# bus.net
KiCad netlist of a schematic drawn in EAGLE
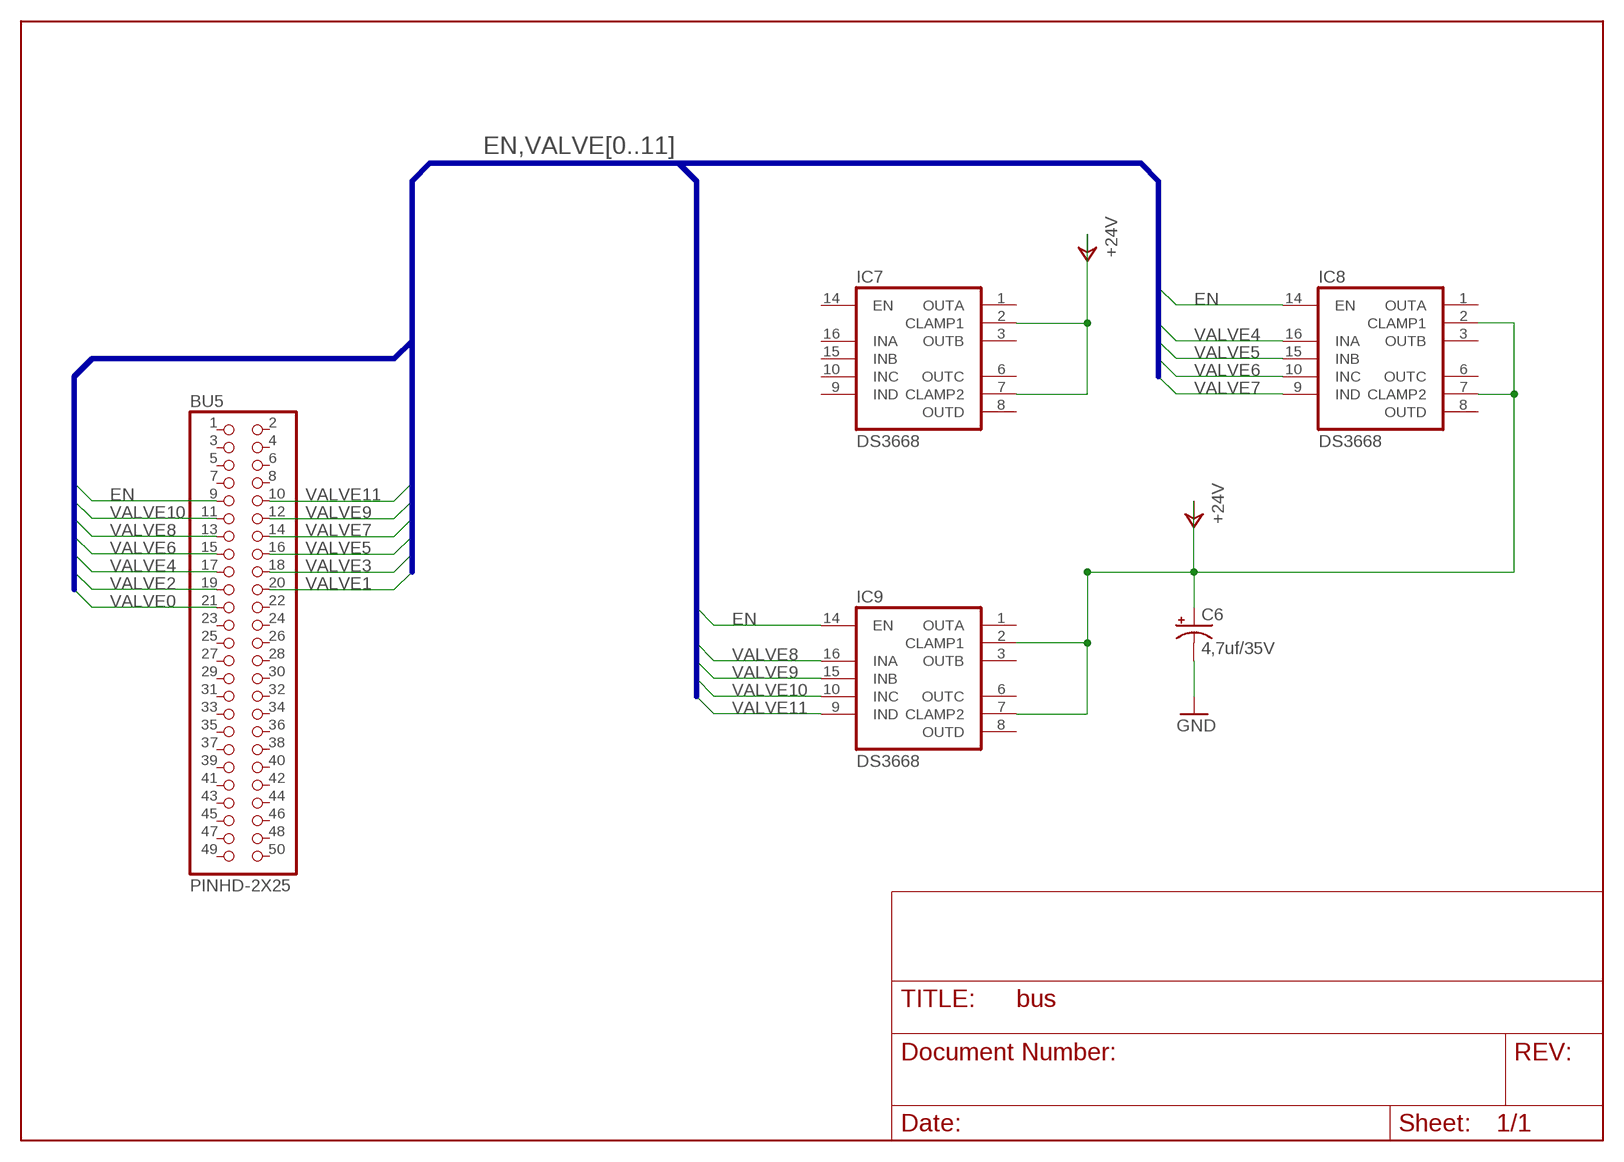
[diagram p0: schematic, sheet 1]

(export (version "E")
  (design (tool "Eeschema 10.0.6"))
  (components
    (comp (ref "BU5")
      (value "PINHD-2X25")
      (footprint "eagle-import:2X25")
      (libsource (lib "eagle-import") (part "PINHD-2X25"))
    )
    (comp (ref "C6")
      (value "4,7uf/35V")
      (footprint "eagle-import:E2,5-6")
      (libsource (lib "eagle-import") (part "CPOL-USE2.5-6"))
    )
    (comp (ref "IC7")
      (value "DS3668")
      (footprint "eagle-import:DIL-16")
      (libsource (lib "eagle-import") (part "DS3668"))
    )
    (comp (ref "IC8")
      (value "DS3668")
      (footprint "eagle-import:DIL-16")
      (libsource (lib "eagle-import") (part "DS3668"))
    )
    (comp (ref "IC9")
      (value "DS3668")
      (footprint "eagle-import:DIL-16")
      (libsource (lib "eagle-import") (part "DS3668"))
    )
  )
  (nets
    (net (code "13") (name "+24V") (class "Default")
      (node (ref "C6") (pin "+") (pinfunction "+_+") (pintype "passive"))
      (node (ref "IC7") (pin "2") (pinfunction "CLAMP1_2") (pintype "bidirectional"))
      (node (ref "IC7") (pin "7") (pinfunction "CLAMP2_7") (pintype "bidirectional"))
      (node (ref "IC8") (pin "2") (pinfunction "CLAMP1_2") (pintype "bidirectional"))
      (node (ref "IC8") (pin "7") (pinfunction "CLAMP2_7") (pintype "bidirectional"))
      (node (ref "IC9") (pin "2") (pinfunction "CLAMP1_2") (pintype "bidirectional"))
      (node (ref "IC9") (pin "7") (pinfunction "CLAMP2_7") (pintype "bidirectional"))
    )
    (net (code "14") (name "/EN") (class "Default")
      (node (ref "BU5") (pin "9") (pinfunction "9_9") (pintype "passive"))
      (node (ref "IC8") (pin "14") (pinfunction "EN_14") (pintype "input"))
      (node (ref "IC9") (pin "14") (pinfunction "EN_14") (pintype "input"))
    )
    (net (code "16") (name "/VALVE0") (class "Default")
      (node (ref "BU5") (pin "21") (pinfunction "21_21") (pintype "passive"))
    )
    (net (code "17") (name "/VALVE1") (class "Default")
      (node (ref "BU5") (pin "20") (pinfunction "20_20") (pintype "passive"))
    )
    (net (code "18") (name "/VALVE2") (class "Default")
      (node (ref "BU5") (pin "19") (pinfunction "19_19") (pintype "passive"))
    )
    (net (code "19") (name "/VALVE3") (class "Default")
      (node (ref "BU5") (pin "18") (pinfunction "18_18") (pintype "passive"))
    )
    (net (code "20") (name "/VALVE4") (class "Default")
      (node (ref "BU5") (pin "17") (pinfunction "17_17") (pintype "passive"))
      (node (ref "IC8") (pin "16") (pinfunction "INA_16") (pintype "input"))
    )
    (net (code "21") (name "/VALVE5") (class "Default")
      (node (ref "BU5") (pin "16") (pinfunction "16_16") (pintype "passive"))
      (node (ref "IC8") (pin "15") (pinfunction "INB_15") (pintype "input"))
    )
    (net (code "22") (name "/VALVE6") (class "Default")
      (node (ref "BU5") (pin "15") (pinfunction "15_15") (pintype "passive"))
      (node (ref "IC8") (pin "10") (pinfunction "INC_10") (pintype "input"))
    )
    (net (code "23") (name "/VALVE7") (class "Default")
      (node (ref "BU5") (pin "14") (pinfunction "14_14") (pintype "passive"))
      (node (ref "IC8") (pin "9") (pinfunction "IND_9") (pintype "input"))
    )
    (net (code "24") (name "/VALVE8") (class "Default")
      (node (ref "BU5") (pin "13") (pinfunction "13_13") (pintype "passive"))
      (node (ref "IC9") (pin "16") (pinfunction "INA_16") (pintype "input"))
    )
    (net (code "25") (name "/VALVE9") (class "Default")
      (node (ref "BU5") (pin "12") (pinfunction "12_12") (pintype "passive"))
      (node (ref "IC9") (pin "15") (pinfunction "INB_15") (pintype "input"))
    )
    (net (code "26") (name "/VALVE10") (class "Default")
      (node (ref "BU5") (pin "11") (pinfunction "11_11") (pintype "passive"))
      (node (ref "IC9") (pin "10") (pinfunction "INC_10") (pintype "input"))
    )
    (net (code "27") (name "/VALVE11") (class "Default")
      (node (ref "BU5") (pin "10") (pinfunction "10_10") (pintype "passive"))
      (node (ref "IC9") (pin "9") (pinfunction "IND_9") (pintype "input"))
    )
    (net (code "28") (name "GND") (class "Default")
      (node (ref "C6") (pin "-") (pinfunction "-_-") (pintype "passive"))
    )
    (net (code "29") (name "unconnected-(BU5-Pad1)") (class "Default")
      (node (ref "BU5") (pin "1") (pinfunction "1_1") (pintype "passive"))
    )
    (net (code "30") (name "unconnected-(BU5-Pad2)") (class "Default")
      (node (ref "BU5") (pin "2") (pinfunction "2_2") (pintype "passive"))
    )
    (net (code "31") (name "unconnected-(BU5-Pad3)") (class "Default")
      (node (ref "BU5") (pin "3") (pinfunction "3_3") (pintype "passive"))
    )
    (net (code "32") (name "unconnected-(BU5-Pad4)") (class "Default")
      (node (ref "BU5") (pin "4") (pinfunction "4_4") (pintype "passive"))
    )
    (net (code "33") (name "unconnected-(BU5-Pad5)") (class "Default")
      (node (ref "BU5") (pin "5") (pinfunction "5_5") (pintype "passive"))
    )
    (net (code "34") (name "unconnected-(BU5-Pad6)") (class "Default")
      (node (ref "BU5") (pin "6") (pinfunction "6_6") (pintype "passive"))
    )
    (net (code "35") (name "unconnected-(BU5-Pad7)") (class "Default")
      (node (ref "BU5") (pin "7") (pinfunction "7_7") (pintype "passive"))
    )
    (net (code "36") (name "unconnected-(BU5-Pad8)") (class "Default")
      (node (ref "BU5") (pin "8") (pinfunction "8_8") (pintype "passive"))
    )
    (net (code "37") (name "unconnected-(BU5-Pad22)") (class "Default")
      (node (ref "BU5") (pin "22") (pinfunction "22_22") (pintype "passive"))
    )
    (net (code "38") (name "unconnected-(BU5-Pad23)") (class "Default")
      (node (ref "BU5") (pin "23") (pinfunction "23_23") (pintype "passive"))
    )
    (net (code "39") (name "unconnected-(BU5-Pad24)") (class "Default")
      (node (ref "BU5") (pin "24") (pinfunction "24_24") (pintype "passive"))
    )
    (net (code "40") (name "unconnected-(BU5-Pad25)") (class "Default")
      (node (ref "BU5") (pin "25") (pinfunction "25_25") (pintype "passive"))
    )
    (net (code "41") (name "unconnected-(BU5-Pad26)") (class "Default")
      (node (ref "BU5") (pin "26") (pinfunction "26_26") (pintype "passive"))
    )
    (net (code "42") (name "unconnected-(BU5-Pad27)") (class "Default")
      (node (ref "BU5") (pin "27") (pinfunction "27_27") (pintype "passive"))
    )
    (net (code "43") (name "unconnected-(BU5-Pad28)") (class "Default")
      (node (ref "BU5") (pin "28") (pinfunction "28_28") (pintype "passive"))
    )
    (net (code "44") (name "unconnected-(BU5-Pad29)") (class "Default")
      (node (ref "BU5") (pin "29") (pinfunction "29_29") (pintype "passive"))
    )
    (net (code "45") (name "unconnected-(BU5-Pad30)") (class "Default")
      (node (ref "BU5") (pin "30") (pinfunction "30_30") (pintype "passive"))
    )
    (net (code "46") (name "unconnected-(BU5-Pad31)") (class "Default")
      (node (ref "BU5") (pin "31") (pinfunction "31_31") (pintype "passive"))
    )
    (net (code "47") (name "unconnected-(BU5-Pad32)") (class "Default")
      (node (ref "BU5") (pin "32") (pinfunction "32_32") (pintype "passive"))
    )
    (net (code "48") (name "unconnected-(BU5-Pad33)") (class "Default")
      (node (ref "BU5") (pin "33") (pinfunction "33_33") (pintype "passive"))
    )
    (net (code "49") (name "unconnected-(BU5-Pad34)") (class "Default")
      (node (ref "BU5") (pin "34") (pinfunction "34_34") (pintype "passive"))
    )
    (net (code "50") (name "unconnected-(BU5-Pad35)") (class "Default")
      (node (ref "BU5") (pin "35") (pinfunction "35_35") (pintype "passive"))
    )
    (net (code "51") (name "unconnected-(BU5-Pad36)") (class "Default")
      (node (ref "BU5") (pin "36") (pinfunction "36_36") (pintype "passive"))
    )
    (net (code "52") (name "unconnected-(BU5-Pad37)") (class "Default")
      (node (ref "BU5") (pin "37") (pinfunction "37_37") (pintype "passive"))
    )
    (net (code "53") (name "unconnected-(BU5-Pad38)") (class "Default")
      (node (ref "BU5") (pin "38") (pinfunction "38_38") (pintype "passive"))
    )
    (net (code "54") (name "unconnected-(BU5-Pad39)") (class "Default")
      (node (ref "BU5") (pin "39") (pinfunction "39_39") (pintype "passive"))
    )
    (net (code "55") (name "unconnected-(BU5-Pad40)") (class "Default")
      (node (ref "BU5") (pin "40") (pinfunction "40_40") (pintype "passive"))
    )
    (net (code "56") (name "unconnected-(BU5-Pad41)") (class "Default")
      (node (ref "BU5") (pin "41") (pinfunction "41_41") (pintype "passive"))
    )
    (net (code "57") (name "unconnected-(BU5-Pad42)") (class "Default")
      (node (ref "BU5") (pin "42") (pinfunction "42_42") (pintype "passive"))
    )
    (net (code "58") (name "unconnected-(BU5-Pad43)") (class "Default")
      (node (ref "BU5") (pin "43") (pinfunction "43_43") (pintype "passive"))
    )
    (net (code "59") (name "unconnected-(BU5-Pad44)") (class "Default")
      (node (ref "BU5") (pin "44") (pinfunction "44_44") (pintype "passive"))
    )
    (net (code "60") (name "unconnected-(BU5-Pad45)") (class "Default")
      (node (ref "BU5") (pin "45") (pinfunction "45_45") (pintype "passive"))
    )
    (net (code "61") (name "unconnected-(BU5-Pad46)") (class "Default")
      (node (ref "BU5") (pin "46") (pinfunction "46_46") (pintype "passive"))
    )
    (net (code "62") (name "unconnected-(BU5-Pad47)") (class "Default")
      (node (ref "BU5") (pin "47") (pinfunction "47_47") (pintype "passive"))
    )
    (net (code "63") (name "unconnected-(BU5-Pad48)") (class "Default")
      (node (ref "BU5") (pin "48") (pinfunction "48_48") (pintype "passive"))
    )
    (net (code "64") (name "unconnected-(BU5-Pad49)") (class "Default")
      (node (ref "BU5") (pin "49") (pinfunction "49_49") (pintype "passive"))
    )
    (net (code "65") (name "unconnected-(BU5-Pad50)") (class "Default")
      (node (ref "BU5") (pin "50") (pinfunction "50_50") (pintype "passive"))
    )
    (net (code "66") (name "unconnected-(IC7A-EN-Pad14)") (class "Default")
      (node (ref "IC7") (pin "14") (pinfunction "EN_14") (pintype "input"))
    )
    (net (code "67") (name "unconnected-(IC7A-INA-Pad16)") (class "Default")
      (node (ref "IC7") (pin "16") (pinfunction "INA_16") (pintype "input"))
    )
    (net (code "68") (name "unconnected-(IC7A-INB-Pad15)") (class "Default")
      (node (ref "IC7") (pin "15") (pinfunction "INB_15") (pintype "input"))
    )
    (net (code "69") (name "unconnected-(IC7A-INC-Pad10)") (class "Default")
      (node (ref "IC7") (pin "10") (pinfunction "INC_10") (pintype "input"))
    )
    (net (code "70") (name "unconnected-(IC7A-IND-Pad9)") (class "Default")
      (node (ref "IC7") (pin "9") (pinfunction "IND_9") (pintype "input"))
    )
    (net (code "71") (name "unconnected-(IC7A-OUTA-Pad1)") (class "Default")
      (node (ref "IC7") (pin "1") (pinfunction "OUTA_1") (pintype "bidirectional"))
    )
    (net (code "72") (name "unconnected-(IC7A-OUTB-Pad3)") (class "Default")
      (node (ref "IC7") (pin "3") (pinfunction "OUTB_3") (pintype "bidirectional"))
    )
    (net (code "73") (name "unconnected-(IC7A-OUTC-Pad6)") (class "Default")
      (node (ref "IC7") (pin "6") (pinfunction "OUTC_6") (pintype "bidirectional"))
    )
    (net (code "74") (name "unconnected-(IC7A-OUTD-Pad8)") (class "Default")
      (node (ref "IC7") (pin "8") (pinfunction "OUTD_8") (pintype "bidirectional"))
    )
    (net (code "75") (name "unconnected-(IC8A-OUTA-Pad1)") (class "Default")
      (node (ref "IC8") (pin "1") (pinfunction "OUTA_1") (pintype "bidirectional"))
    )
    (net (code "76") (name "unconnected-(IC8A-OUTB-Pad3)") (class "Default")
      (node (ref "IC8") (pin "3") (pinfunction "OUTB_3") (pintype "bidirectional"))
    )
    (net (code "77") (name "unconnected-(IC8A-OUTC-Pad6)") (class "Default")
      (node (ref "IC8") (pin "6") (pinfunction "OUTC_6") (pintype "bidirectional"))
    )
    (net (code "78") (name "unconnected-(IC8A-OUTD-Pad8)") (class "Default")
      (node (ref "IC8") (pin "8") (pinfunction "OUTD_8") (pintype "bidirectional"))
    )
    (net (code "79") (name "unconnected-(IC9A-OUTA-Pad1)") (class "Default")
      (node (ref "IC9") (pin "1") (pinfunction "OUTA_1") (pintype "bidirectional"))
    )
    (net (code "80") (name "unconnected-(IC9A-OUTB-Pad3)") (class "Default")
      (node (ref "IC9") (pin "3") (pinfunction "OUTB_3") (pintype "bidirectional"))
    )
    (net (code "81") (name "unconnected-(IC9A-OUTC-Pad6)") (class "Default")
      (node (ref "IC9") (pin "6") (pinfunction "OUTC_6") (pintype "bidirectional"))
    )
    (net (code "82") (name "unconnected-(IC9A-OUTD-Pad8)") (class "Default")
      (node (ref "IC9") (pin "8") (pinfunction "OUTD_8") (pintype "bidirectional"))
    )
  )
)
